# circuitPendulumLEDs.net
KiCad netlist of a schematic drawn in EAGLE
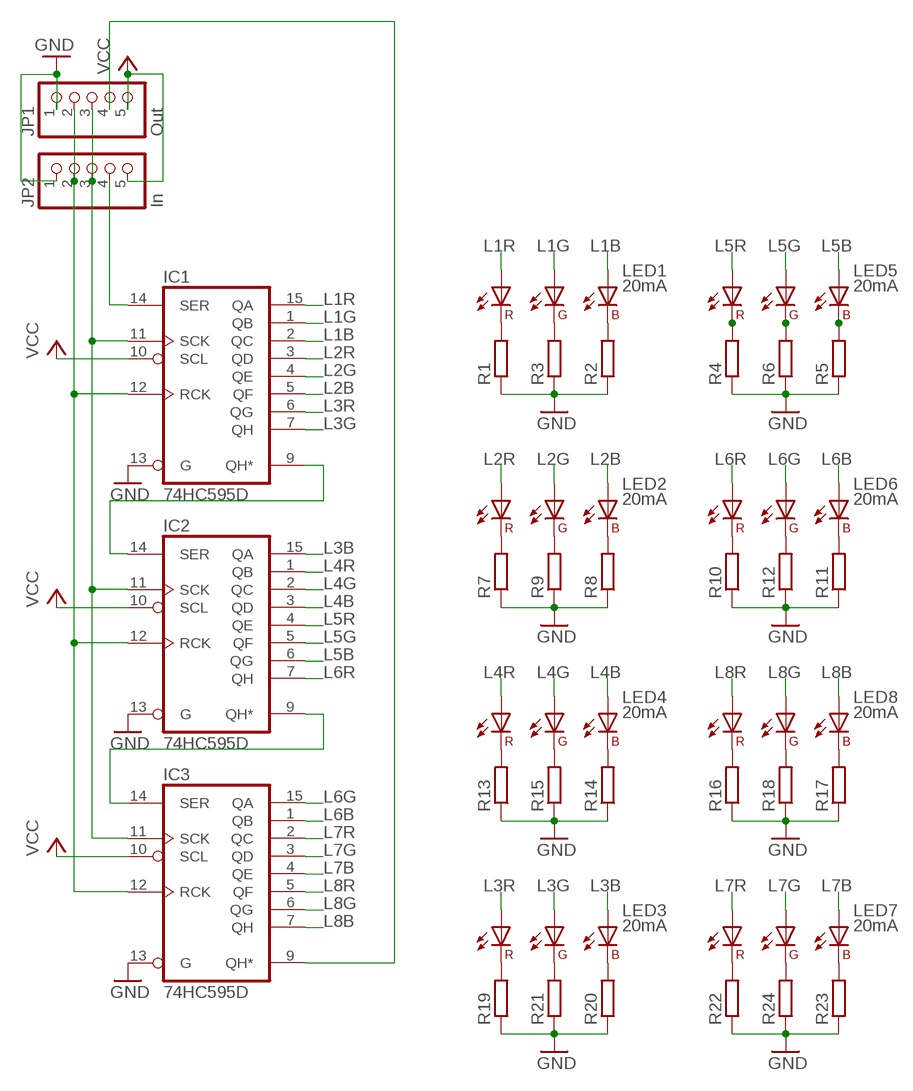
[diagram p0: schematic, sheet 1]

(export (version "E")
  (design (tool "Eeschema 10.0.6"))
  (components
    (comp (ref "IC1")
      (value "74HC595D")
      (footprint "eagle-import:SO16")
      (libsource (lib "eagle-import") (part "74595DHC"))
    )
    (comp (ref "IC2")
      (value "74HC595D")
      (footprint "eagle-import:SO16")
      (libsource (lib "eagle-import") (part "74595DHC"))
    )
    (comp (ref "IC3")
      (value "74HC595D")
      (footprint "eagle-import:SO16")
      (libsource (lib "eagle-import") (part "74595DHC"))
    )
    (comp (ref "JP1")
      (value "Out")
      (footprint "eagle-import:1_05X2MM")
      (libsource (lib "eagle-import") (part "PINHD-1X55X2MM"))
    )
    (comp (ref "JP2")
      (value "In")
      (footprint "eagle-import:1_05X2MM")
      (libsource (lib "eagle-import") (part "PINHD-1X55X2MM"))
    )
    (comp (ref "LED1")
      (value "20mA")
      (footprint "eagle-import:PLCC-6_SAMSUNG")
      (libsource (lib "eagle-import") (part "PLCC-6-RGB-SAMSUNG"))
    )
    (comp (ref "LED2")
      (value "20mA")
      (footprint "eagle-import:PLCC-6_SAMSUNG")
      (libsource (lib "eagle-import") (part "PLCC-6-RGB-SAMSUNG"))
    )
    (comp (ref "LED3")
      (value "20mA")
      (footprint "eagle-import:PLCC-6_SAMSUNG")
      (libsource (lib "eagle-import") (part "PLCC-6-RGB-SAMSUNG"))
    )
    (comp (ref "LED4")
      (value "20mA")
      (footprint "eagle-import:PLCC-6_SAMSUNG")
      (libsource (lib "eagle-import") (part "PLCC-6-RGB-SAMSUNG"))
    )
    (comp (ref "LED5")
      (value "20mA")
      (footprint "eagle-import:PLCC-6_SAMSUNG")
      (libsource (lib "eagle-import") (part "PLCC-6-RGB-SAMSUNG"))
    )
    (comp (ref "LED6")
      (value "20mA")
      (footprint "eagle-import:PLCC-6_SAMSUNG")
      (libsource (lib "eagle-import") (part "PLCC-6-RGB-SAMSUNG"))
    )
    (comp (ref "LED7")
      (value "20mA")
      (footprint "eagle-import:PLCC-6_SAMSUNG")
      (libsource (lib "eagle-import") (part "PLCC-6-RGB-SAMSUNG"))
    )
    (comp (ref "LED8")
      (value "20mA")
      (footprint "eagle-import:PLCC-6_SAMSUNG")
      (libsource (lib "eagle-import") (part "PLCC-6-RGB-SAMSUNG"))
    )
    (comp (ref "R1")
      (value "R-EU_R0603")
      (footprint "eagle-import:R0603")
      (libsource (lib "eagle-import") (part "R-EU_R0603"))
    )
    (comp (ref "R2")
      (value "R-EU_R0603")
      (footprint "eagle-import:R0603")
      (libsource (lib "eagle-import") (part "R-EU_R0603"))
    )
    (comp (ref "R3")
      (value "R-EU_R0603")
      (footprint "eagle-import:R0603")
      (libsource (lib "eagle-import") (part "R-EU_R0603"))
    )
    (comp (ref "R4")
      (value "R-EU_R0603")
      (footprint "eagle-import:R0603")
      (libsource (lib "eagle-import") (part "R-EU_R0603"))
    )
    (comp (ref "R5")
      (value "R-EU_R0603")
      (footprint "eagle-import:R0603")
      (libsource (lib "eagle-import") (part "R-EU_R0603"))
    )
    (comp (ref "R6")
      (value "R-EU_R0603")
      (footprint "eagle-import:R0603")
      (libsource (lib "eagle-import") (part "R-EU_R0603"))
    )
    (comp (ref "R7")
      (value "R-EU_R0603")
      (footprint "eagle-import:R0603")
      (libsource (lib "eagle-import") (part "R-EU_R0603"))
    )
    (comp (ref "R8")
      (value "R-EU_R0603")
      (footprint "eagle-import:R0603")
      (libsource (lib "eagle-import") (part "R-EU_R0603"))
    )
    (comp (ref "R9")
      (value "R-EU_R0603")
      (footprint "eagle-import:R0603")
      (libsource (lib "eagle-import") (part "R-EU_R0603"))
    )
    (comp (ref "R10")
      (value "R-EU_R0603")
      (footprint "eagle-import:R0603")
      (libsource (lib "eagle-import") (part "R-EU_R0603"))
    )
    (comp (ref "R11")
      (value "R-EU_R0603")
      (footprint "eagle-import:R0603")
      (libsource (lib "eagle-import") (part "R-EU_R0603"))
    )
    (comp (ref "R12")
      (value "R-EU_R0603")
      (footprint "eagle-import:R0603")
      (libsource (lib "eagle-import") (part "R-EU_R0603"))
    )
    (comp (ref "R13")
      (value "R-EU_R0603")
      (footprint "eagle-import:R0603")
      (libsource (lib "eagle-import") (part "R-EU_R0603"))
    )
    (comp (ref "R14")
      (value "R-EU_R0603")
      (footprint "eagle-import:R0603")
      (libsource (lib "eagle-import") (part "R-EU_R0603"))
    )
    (comp (ref "R15")
      (value "R-EU_R0603")
      (footprint "eagle-import:R0603")
      (libsource (lib "eagle-import") (part "R-EU_R0603"))
    )
    (comp (ref "R16")
      (value "R-EU_R0603")
      (footprint "eagle-import:R0603")
      (libsource (lib "eagle-import") (part "R-EU_R0603"))
    )
    (comp (ref "R17")
      (value "R-EU_R0603")
      (footprint "eagle-import:R0603")
      (libsource (lib "eagle-import") (part "R-EU_R0603"))
    )
    (comp (ref "R18")
      (value "R-EU_R0603")
      (footprint "eagle-import:R0603")
      (libsource (lib "eagle-import") (part "R-EU_R0603"))
    )
    (comp (ref "R19")
      (value "R-EU_R0603")
      (footprint "eagle-import:R0603")
      (libsource (lib "eagle-import") (part "R-EU_R0603"))
    )
    (comp (ref "R20")
      (value "R-EU_R0603")
      (footprint "eagle-import:R0603")
      (libsource (lib "eagle-import") (part "R-EU_R0603"))
    )
    (comp (ref "R21")
      (value "R-EU_R0603")
      (footprint "eagle-import:R0603")
      (libsource (lib "eagle-import") (part "R-EU_R0603"))
    )
    (comp (ref "R22")
      (value "R-EU_R0603")
      (footprint "eagle-import:R0603")
      (libsource (lib "eagle-import") (part "R-EU_R0603"))
    )
    (comp (ref "R23")
      (value "R-EU_R0603")
      (footprint "eagle-import:R0603")
      (libsource (lib "eagle-import") (part "R-EU_R0603"))
    )
    (comp (ref "R24")
      (value "R-EU_R0603")
      (footprint "eagle-import:R0603")
      (libsource (lib "eagle-import") (part "R-EU_R0603"))
    )
  )
  (nets
    (net (code "1") (name "/L1B") (class "Default")
      (node (ref "IC1") (pin "2") (pinfunction "QC_2") (pintype "tri_state"))
      (node (ref "LED1") (pin "3") (pinfunction "AB_3") (pintype "passive"))
    )
    (net (code "2") (name "/L1G") (class "Default")
      (node (ref "IC1") (pin "1") (pinfunction "QB_1") (pintype "tri_state"))
      (node (ref "LED1") (pin "2") (pinfunction "AG_2") (pintype "passive"))
    )
    (net (code "3") (name "/L1R") (class "Default")
      (node (ref "IC1") (pin "15") (pinfunction "QA_15") (pintype "tri_state"))
      (node (ref "LED1") (pin "1") (pinfunction "AR_1") (pintype "passive"))
    )
    (net (code "4") (name "/L2B") (class "Default")
      (node (ref "IC1") (pin "5") (pinfunction "QF_5") (pintype "tri_state"))
      (node (ref "LED2") (pin "3") (pinfunction "AB_3") (pintype "passive"))
    )
    (net (code "5") (name "/L2G") (class "Default")
      (node (ref "IC1") (pin "4") (pinfunction "QE_4") (pintype "tri_state"))
      (node (ref "LED2") (pin "2") (pinfunction "AG_2") (pintype "passive"))
    )
    (net (code "6") (name "/L2R") (class "Default")
      (node (ref "IC1") (pin "3") (pinfunction "QD_3") (pintype "tri_state"))
      (node (ref "LED2") (pin "1") (pinfunction "AR_1") (pintype "passive"))
    )
    (net (code "7") (name "/L3B") (class "Default")
      (node (ref "IC2") (pin "15") (pinfunction "QA_15") (pintype "tri_state"))
      (node (ref "LED3") (pin "3") (pinfunction "AB_3") (pintype "passive"))
    )
    (net (code "8") (name "/L3G") (class "Default")
      (node (ref "IC1") (pin "7") (pinfunction "QH_7") (pintype "tri_state"))
      (node (ref "LED3") (pin "2") (pinfunction "AG_2") (pintype "passive"))
    )
    (net (code "9") (name "/L3R") (class "Default")
      (node (ref "IC1") (pin "6") (pinfunction "QG_6") (pintype "tri_state"))
      (node (ref "LED3") (pin "1") (pinfunction "AR_1") (pintype "passive"))
    )
    (net (code "10") (name "/L4B") (class "Default")
      (node (ref "IC2") (pin "3") (pinfunction "QD_3") (pintype "tri_state"))
      (node (ref "LED4") (pin "3") (pinfunction "AB_3") (pintype "passive"))
    )
    (net (code "11") (name "/L4G") (class "Default")
      (node (ref "IC2") (pin "2") (pinfunction "QC_2") (pintype "tri_state"))
      (node (ref "LED4") (pin "2") (pinfunction "AG_2") (pintype "passive"))
    )
    (net (code "12") (name "/L4R") (class "Default")
      (node (ref "IC2") (pin "1") (pinfunction "QB_1") (pintype "tri_state"))
      (node (ref "LED4") (pin "1") (pinfunction "AR_1") (pintype "passive"))
    )
    (net (code "13") (name "/L5B") (class "Default")
      (node (ref "IC2") (pin "6") (pinfunction "QG_6") (pintype "tri_state"))
      (node (ref "LED5") (pin "3") (pinfunction "AB_3") (pintype "passive"))
    )
    (net (code "14") (name "/L5G") (class "Default")
      (node (ref "IC2") (pin "5") (pinfunction "QF_5") (pintype "tri_state"))
      (node (ref "LED5") (pin "2") (pinfunction "AG_2") (pintype "passive"))
    )
    (net (code "15") (name "/L5R") (class "Default")
      (node (ref "IC2") (pin "4") (pinfunction "QE_4") (pintype "tri_state"))
      (node (ref "LED5") (pin "1") (pinfunction "AR_1") (pintype "passive"))
    )
    (net (code "16") (name "/L6B") (class "Default")
      (node (ref "IC3") (pin "1") (pinfunction "QB_1") (pintype "tri_state"))
      (node (ref "LED6") (pin "3") (pinfunction "AB_3") (pintype "passive"))
    )
    (net (code "17") (name "/L6G") (class "Default")
      (node (ref "IC3") (pin "15") (pinfunction "QA_15") (pintype "tri_state"))
      (node (ref "LED6") (pin "2") (pinfunction "AG_2") (pintype "passive"))
    )
    (net (code "18") (name "/L6R") (class "Default")
      (node (ref "IC2") (pin "7") (pinfunction "QH_7") (pintype "tri_state"))
      (node (ref "LED6") (pin "1") (pinfunction "AR_1") (pintype "passive"))
    )
    (net (code "19") (name "/L7B") (class "Default")
      (node (ref "IC3") (pin "4") (pinfunction "QE_4") (pintype "tri_state"))
      (node (ref "LED7") (pin "3") (pinfunction "AB_3") (pintype "passive"))
    )
    (net (code "20") (name "/L7G") (class "Default")
      (node (ref "IC3") (pin "3") (pinfunction "QD_3") (pintype "tri_state"))
      (node (ref "LED7") (pin "2") (pinfunction "AG_2") (pintype "passive"))
    )
    (net (code "21") (name "/L7R") (class "Default")
      (node (ref "IC3") (pin "2") (pinfunction "QC_2") (pintype "tri_state"))
      (node (ref "LED7") (pin "1") (pinfunction "AR_1") (pintype "passive"))
    )
    (net (code "22") (name "/L8B") (class "Default")
      (node (ref "IC3") (pin "7") (pinfunction "QH_7") (pintype "tri_state"))
      (node (ref "LED8") (pin "3") (pinfunction "AB_3") (pintype "passive"))
    )
    (net (code "23") (name "/L8G") (class "Default")
      (node (ref "IC3") (pin "6") (pinfunction "QG_6") (pintype "tri_state"))
      (node (ref "LED8") (pin "2") (pinfunction "AG_2") (pintype "passive"))
    )
    (net (code "24") (name "/L8R") (class "Default")
      (node (ref "IC3") (pin "5") (pinfunction "QF_5") (pintype "tri_state"))
      (node (ref "LED8") (pin "1") (pinfunction "AR_1") (pintype "passive"))
    )
    (net (code "25") (name "GND") (class "Default")
      (node (ref "IC1") (pin "13") (pinfunction "G_13") (pintype "input"))
      (node (ref "IC2") (pin "13") (pinfunction "G_13") (pintype "input"))
      (node (ref "IC3") (pin "13") (pinfunction "G_13") (pintype "input"))
      (node (ref "JP1") (pin "1") (pinfunction "1_1") (pintype "passive"))
      (node (ref "JP2") (pin "1") (pinfunction "1_1") (pintype "passive"))
      (node (ref "R1") (pin "1") (pinfunction "1_1") (pintype "passive"))
      (node (ref "R10") (pin "1") (pinfunction "1_1") (pintype "passive"))
      (node (ref "R11") (pin "1") (pinfunction "1_1") (pintype "passive"))
      (node (ref "R12") (pin "1") (pinfunction "1_1") (pintype "passive"))
      (node (ref "R13") (pin "1") (pinfunction "1_1") (pintype "passive"))
      (node (ref "R14") (pin "1") (pinfunction "1_1") (pintype "passive"))
      (node (ref "R15") (pin "1") (pinfunction "1_1") (pintype "passive"))
      (node (ref "R16") (pin "1") (pinfunction "1_1") (pintype "passive"))
      (node (ref "R17") (pin "1") (pinfunction "1_1") (pintype "passive"))
      (node (ref "R18") (pin "1") (pinfunction "1_1") (pintype "passive"))
      (node (ref "R19") (pin "1") (pinfunction "1_1") (pintype "passive"))
      (node (ref "R2") (pin "1") (pinfunction "1_1") (pintype "passive"))
      (node (ref "R20") (pin "1") (pinfunction "1_1") (pintype "passive"))
      (node (ref "R21") (pin "1") (pinfunction "1_1") (pintype "passive"))
      (node (ref "R22") (pin "1") (pinfunction "1_1") (pintype "passive"))
      (node (ref "R23") (pin "1") (pinfunction "1_1") (pintype "passive"))
      (node (ref "R24") (pin "1") (pinfunction "1_1") (pintype "passive"))
      (node (ref "R3") (pin "1") (pinfunction "1_1") (pintype "passive"))
      (node (ref "R4") (pin "1") (pinfunction "1_1") (pintype "passive"))
      (node (ref "R5") (pin "1") (pinfunction "1_1") (pintype "passive"))
      (node (ref "R6") (pin "1") (pinfunction "1_1") (pintype "passive"))
      (node (ref "R7") (pin "1") (pinfunction "1_1") (pintype "passive"))
      (node (ref "R8") (pin "1") (pinfunction "1_1") (pintype "passive"))
      (node (ref "R9") (pin "1") (pinfunction "1_1") (pintype "passive"))
    )
    (net (code "26") (name "Net-(IC1A-QH*)") (class "Default")
      (node (ref "IC1") (pin "9") (pinfunction "QH*_9") (pintype "tri_state"))
      (node (ref "IC2") (pin "14") (pinfunction "SER_14") (pintype "input"))
    )
    (net (code "27") (name "Net-(IC1A-RCK)") (class "Default")
      (node (ref "IC1") (pin "12") (pinfunction "RCK_12") (pintype "input"))
      (node (ref "IC2") (pin "12") (pinfunction "RCK_12") (pintype "input"))
      (node (ref "IC3") (pin "12") (pinfunction "RCK_12") (pintype "input"))
      (node (ref "JP1") (pin "2") (pinfunction "2_2") (pintype "passive"))
      (node (ref "JP2") (pin "2") (pinfunction "2_2") (pintype "passive"))
    )
    (net (code "28") (name "Net-(IC1A-SCK)") (class "Default")
      (node (ref "IC1") (pin "11") (pinfunction "SCK_11") (pintype "input"))
      (node (ref "IC2") (pin "11") (pinfunction "SCK_11") (pintype "input"))
      (node (ref "IC3") (pin "11") (pinfunction "SCK_11") (pintype "input"))
      (node (ref "JP1") (pin "3") (pinfunction "3_3") (pintype "passive"))
      (node (ref "JP2") (pin "3") (pinfunction "3_3") (pintype "passive"))
    )
    (net (code "29") (name "Net-(IC1A-SER)") (class "Default")
      (node (ref "IC1") (pin "14") (pinfunction "SER_14") (pintype "input"))
      (node (ref "JP2") (pin "4") (pinfunction "4_4") (pintype "passive"))
    )
    (net (code "30") (name "Net-(IC2A-QH*)") (class "Default")
      (node (ref "IC2") (pin "9") (pinfunction "QH*_9") (pintype "tri_state"))
      (node (ref "IC3") (pin "14") (pinfunction "SER_14") (pintype "input"))
    )
    (net (code "31") (name "Net-(IC3A-QH*)") (class "Default")
      (node (ref "IC3") (pin "9") (pinfunction "QH*_9") (pintype "tri_state"))
      (node (ref "JP1") (pin "4") (pinfunction "4_4") (pintype "passive"))
    )
    (net (code "32") (name "Net-(LED1-CB)") (class "Default")
      (node (ref "LED1") (pin "6") (pinfunction "CB_6") (pintype "passive"))
      (node (ref "R2") (pin "2") (pinfunction "2_2") (pintype "passive"))
    )
    (net (code "33") (name "Net-(LED1-CG)") (class "Default")
      (node (ref "LED1") (pin "5") (pinfunction "CG_5") (pintype "passive"))
      (node (ref "R3") (pin "2") (pinfunction "2_2") (pintype "passive"))
    )
    (net (code "34") (name "Net-(LED1-CR)") (class "Default")
      (node (ref "LED1") (pin "4") (pinfunction "CR_4") (pintype "passive"))
      (node (ref "R1") (pin "2") (pinfunction "2_2") (pintype "passive"))
    )
    (net (code "35") (name "Net-(LED2-CB)") (class "Default")
      (node (ref "LED2") (pin "6") (pinfunction "CB_6") (pintype "passive"))
      (node (ref "R8") (pin "2") (pinfunction "2_2") (pintype "passive"))
    )
    (net (code "36") (name "Net-(LED2-CG)") (class "Default")
      (node (ref "LED2") (pin "5") (pinfunction "CG_5") (pintype "passive"))
      (node (ref "R9") (pin "2") (pinfunction "2_2") (pintype "passive"))
    )
    (net (code "37") (name "Net-(LED2-CR)") (class "Default")
      (node (ref "LED2") (pin "4") (pinfunction "CR_4") (pintype "passive"))
      (node (ref "R7") (pin "2") (pinfunction "2_2") (pintype "passive"))
    )
    (net (code "38") (name "Net-(LED3-CB)") (class "Default")
      (node (ref "LED3") (pin "6") (pinfunction "CB_6") (pintype "passive"))
      (node (ref "R20") (pin "2") (pinfunction "2_2") (pintype "passive"))
    )
    (net (code "39") (name "Net-(LED3-CG)") (class "Default")
      (node (ref "LED3") (pin "5") (pinfunction "CG_5") (pintype "passive"))
      (node (ref "R21") (pin "2") (pinfunction "2_2") (pintype "passive"))
    )
    (net (code "40") (name "Net-(LED3-CR)") (class "Default")
      (node (ref "LED3") (pin "4") (pinfunction "CR_4") (pintype "passive"))
      (node (ref "R19") (pin "2") (pinfunction "2_2") (pintype "passive"))
    )
    (net (code "41") (name "Net-(LED4-CB)") (class "Default")
      (node (ref "LED4") (pin "6") (pinfunction "CB_6") (pintype "passive"))
      (node (ref "R14") (pin "2") (pinfunction "2_2") (pintype "passive"))
    )
    (net (code "42") (name "Net-(LED4-CG)") (class "Default")
      (node (ref "LED4") (pin "5") (pinfunction "CG_5") (pintype "passive"))
      (node (ref "R15") (pin "2") (pinfunction "2_2") (pintype "passive"))
    )
    (net (code "43") (name "Net-(LED4-CR)") (class "Default")
      (node (ref "LED4") (pin "4") (pinfunction "CR_4") (pintype "passive"))
      (node (ref "R13") (pin "2") (pinfunction "2_2") (pintype "passive"))
    )
    (net (code "44") (name "Net-(LED5-CB)") (class "Default")
      (node (ref "LED5") (pin "6") (pinfunction "CB_6") (pintype "passive"))
      (node (ref "R5") (pin "2") (pinfunction "2_2") (pintype "passive"))
    )
    (net (code "45") (name "Net-(LED5-CG)") (class "Default")
      (node (ref "LED5") (pin "5") (pinfunction "CG_5") (pintype "passive"))
      (node (ref "R6") (pin "2") (pinfunction "2_2") (pintype "passive"))
    )
    (net (code "46") (name "Net-(LED5-CR)") (class "Default")
      (node (ref "LED5") (pin "4") (pinfunction "CR_4") (pintype "passive"))
      (node (ref "R4") (pin "2") (pinfunction "2_2") (pintype "passive"))
    )
    (net (code "47") (name "Net-(LED6-CB)") (class "Default")
      (node (ref "LED6") (pin "6") (pinfunction "CB_6") (pintype "passive"))
      (node (ref "R11") (pin "2") (pinfunction "2_2") (pintype "passive"))
    )
    (net (code "48") (name "Net-(LED6-CG)") (class "Default")
      (node (ref "LED6") (pin "5") (pinfunction "CG_5") (pintype "passive"))
      (node (ref "R12") (pin "2") (pinfunction "2_2") (pintype "passive"))
    )
    (net (code "49") (name "Net-(LED6-CR)") (class "Default")
      (node (ref "LED6") (pin "4") (pinfunction "CR_4") (pintype "passive"))
      (node (ref "R10") (pin "2") (pinfunction "2_2") (pintype "passive"))
    )
    (net (code "50") (name "Net-(LED7-CB)") (class "Default")
      (node (ref "LED7") (pin "6") (pinfunction "CB_6") (pintype "passive"))
      (node (ref "R23") (pin "2") (pinfunction "2_2") (pintype "passive"))
    )
    (net (code "51") (name "Net-(LED7-CG)") (class "Default")
      (node (ref "LED7") (pin "5") (pinfunction "CG_5") (pintype "passive"))
      (node (ref "R24") (pin "2") (pinfunction "2_2") (pintype "passive"))
    )
    (net (code "52") (name "Net-(LED7-CR)") (class "Default")
      (node (ref "LED7") (pin "4") (pinfunction "CR_4") (pintype "passive"))
      (node (ref "R22") (pin "2") (pinfunction "2_2") (pintype "passive"))
    )
    (net (code "53") (name "Net-(LED8-CB)") (class "Default")
      (node (ref "LED8") (pin "6") (pinfunction "CB_6") (pintype "passive"))
      (node (ref "R17") (pin "2") (pinfunction "2_2") (pintype "passive"))
    )
    (net (code "54") (name "Net-(LED8-CG)") (class "Default")
      (node (ref "LED8") (pin "5") (pinfunction "CG_5") (pintype "passive"))
      (node (ref "R18") (pin "2") (pinfunction "2_2") (pintype "passive"))
    )
    (net (code "55") (name "Net-(LED8-CR)") (class "Default")
      (node (ref "LED8") (pin "4") (pinfunction "CR_4") (pintype "passive"))
      (node (ref "R16") (pin "2") (pinfunction "2_2") (pintype "passive"))
    )
    (net (code "56") (name "VCC") (class "Default")
      (node (ref "IC1") (pin "10") (pinfunction "SCL_10") (pintype "input"))
      (node (ref "IC2") (pin "10") (pinfunction "SCL_10") (pintype "input"))
      (node (ref "IC3") (pin "10") (pinfunction "SCL_10") (pintype "input"))
      (node (ref "JP1") (pin "5") (pinfunction "5_5") (pintype "passive"))
      (node (ref "JP2") (pin "5") (pinfunction "5_5") (pintype "passive"))
    )
  )
)
